# power.net
KiCad netlist of a schematic drawn in Altium Designer
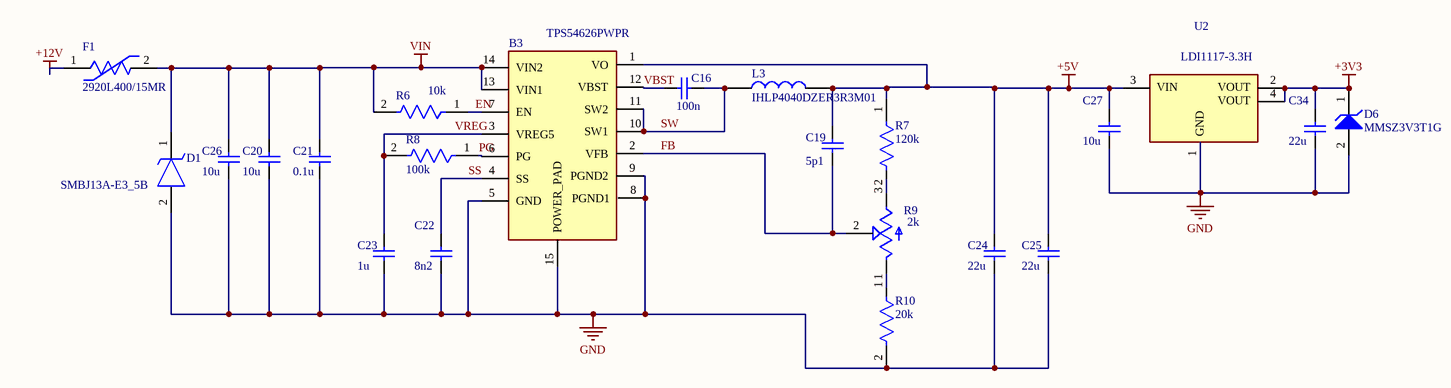
[diagram p0: power.SchDoc]

(export (version "E")
  (design (tool "Eeschema 10.0.6"))
  (components
    (comp (ref "B3")
      (value "TPS54626PWPR")
      (footprint "TPS54626PWPR")
      (fields
        (field (name "MOUSER PART NUMBER") "595-TPS54626PWPR")
        (field (name "MANUFACTURER") "Texas Instruments")
      )
      (libsource (lib "HydrogreenLibrary") (part "TPS54626PWPR"))
    )
    (comp (ref "C16")
      (value "100n")
      (footprint "CAPC1206(3216)150_L")
      (description "CAP 1.8uF 10V ±5% 1206 (3216 Metric) Thickness 1.45mm SMD")
      (fields (field (name "TOLERANCE") "Â±5%"))
      (libsource (lib "Altium Content Vault") (part "CAP"))
    )
    (comp (ref "C19")
      (value "5p1")
      (footprint "CAPC1206(3216)150_L")
      (description "CAP 1.8uF 10V ±5% 1206 (3216 Metric) Thickness 1.45mm SMD")
      (fields (field (name "TOLERANCE") "Â±5%"))
      (libsource (lib "Altium Content Vault") (part "CAP"))
    )
    (comp (ref "C20")
      (value "10u")
      (footprint "CAPC1206(3216)150_L")
      (description "CAP 1.8uF 10V ±5% 1206 (3216 Metric) Thickness 1.45mm SMD")
      (fields (field (name "TOLERANCE") "Â±5%"))
      (libsource (lib "Altium Content Vault") (part "CAP"))
    )
    (comp (ref "C21")
      (value "0.1u")
      (footprint "CAPC1206(3216)150_L")
      (description "CAP 1.8uF 10V ±5% 1206 (3216 Metric) Thickness 1.45mm SMD")
      (fields (field (name "TOLERANCE") "Â±5%"))
      (libsource (lib "Altium Content Vault") (part "CAP"))
    )
    (comp (ref "C22")
      (value "8n2")
      (footprint "CAPC1206(3216)150_L")
      (description "CAP 1.8uF 10V ±5% 1206 (3216 Metric) Thickness 1.45mm SMD")
      (fields (field (name "TOLERANCE") "Â±5%"))
      (libsource (lib "Altium Content Vault") (part "CAP"))
    )
    (comp (ref "C23")
      (value "1u")
      (footprint "CAPC1206(3216)150_L")
      (description "CAP 1.8uF 10V ±5% 1206 (3216 Metric) Thickness 1.45mm SMD")
      (fields (field (name "TOLERANCE") "Â±5%"))
      (libsource (lib "Altium Content Vault") (part "CAP"))
    )
    (comp (ref "C24")
      (value "22u")
      (footprint "CAPC1206(3216)150_L")
      (description "CAP 1.8uF 10V ±5% 1206 (3216 Metric) Thickness 1.45mm SMD")
      (fields (field (name "TOLERANCE") "Â±5%"))
      (libsource (lib "Altium Content Vault") (part "CAP"))
    )
    (comp (ref "C25")
      (value "22u")
      (footprint "CAPC1206(3216)150_L")
      (description "CAP 1.8uF 10V ±5% 1206 (3216 Metric) Thickness 1.45mm SMD")
      (fields (field (name "TOLERANCE") "Â±5%"))
      (libsource (lib "Altium Content Vault") (part "CAP"))
    )
    (comp (ref "C26")
      (value "10u")
      (footprint "CAPC1206(3216)150_L")
      (description "CAP 1.8uF 10V ±5% 1206 (3216 Metric) Thickness 1.45mm SMD")
      (fields (field (name "TOLERANCE") "Â±5%"))
      (libsource (lib "Altium Content Vault") (part "CAP"))
    )
    (comp (ref "C27")
      (value "10u")
      (footprint "CAPC1206(3216)150_L")
      (description "CAP 1.8uF 10V ±5% 1206 (3216 Metric) Thickness 1.45mm SMD")
      (fields (field (name "TOLERANCE") "Â±5%"))
      (libsource (lib "Altium Content Vault") (part "CAP"))
    )
    (comp (ref "C34")
      (value "22u")
      (footprint "CAPC1206(3216)150_L")
      (description "CAP 1.8uF 10V ±5% 1206 (3216 Metric) Thickness 1.45mm SMD")
      (fields (field (name "TOLERANCE") "Â±5%"))
      (libsource (lib "Altium Content Vault") (part "CAP"))
    )
    (comp (ref "D1")
      (value "SMBJ13A-E3_5B")
      (footprint "SamacSys:DIOM5436X244N")
      (description "TVS Diode (Uni-directional)")
      (fields
        (field (name "MANUFACTURER_PART_NUMBER") "SMBJ13A-E3/5B")
        (field (name "MOUSER PART NUMBER") "625-SMBJ13A-E3/5B")
      )
      (libsource (lib "*") (part "SMBJ13A-E3_5B"))
    )
    (comp (ref "D6")
      (value "MMSZ3V3T1G")
      (footprint "ONSC-SOD-123-2-425-04_V")
      (description "Zener Voltage Regulator, 500 mW, 2-Pin SOD-123, Pb-Free, Tape and Reel")
      (fields (field (name "MANUFACTURER") "On Semiconductor"))
      (libsource (lib "Altium Content Vault") (part "ONSC-K1A2-2"))
    )
    (comp (ref "F1")
      (value "2920L400/15MR")
      (footprint "FP-2920L400-15MR-MFG")
      (description "PTC RESET FUSE 15V 4A 2920")
      (libsource (lib "Altium Content Vault") (part "fc31388045fc42ab786d6d00b506e9f"))
    )
    (comp (ref "L3")
      (value "IHLP4040DZER3R3M01")
      (footprint "IHLP4040DZER3R3M01")
      (description "Inductor High Current Shielded Wirewound 3.3uH 20% 100KHz 10A 11.8mOhm DCR 4040 T/R")
      (fields
        (field (name "MOUSER PART NUMBER") "70-IHLP4040DZER3R3M0")
        (field (name "MANUFACTURER") "Vishay")
      )
      (libsource (lib "HydrogreenLibrary") (part "IHLP4040DZER3R3M01"))
    )
    (comp (ref "R6")
      (value "10k")
      (footprint "FP-RK73H2B-MFG")
      (description "40.2kΩ ±1% 0.25W Chip Resistor 1206 Thick Film AEC-Q200 Qualified")
      (fields (field (name "TOLERANCE") "1%"))
      (libsource (lib "Altium Content Vault") (part "1029c3af85768c4190bb7ad29bc67b5"))
    )
    (comp (ref "R7")
      (value "120k")
      (footprint "FP-RK73H2B-MFG")
      (description "40.2kΩ ±1% 0.25W Chip Resistor 1206 Thick Film AEC-Q200 Qualified")
      (fields (field (name "TOLERANCE") "1%"))
      (libsource (lib "Altium Content Vault") (part "1029c3af85768c4190bb7ad29bc67b5"))
    )
    (comp (ref "R8")
      (value "100k")
      (footprint "FP-RK73H2B-MFG")
      (description "40.2kΩ ±1% 0.25W Chip Resistor 1206 Thick Film AEC-Q200 Qualified")
      (fields (field (name "TOLERANCE") "1%"))
      (libsource (lib "Altium Content Vault") (part "1029c3af85768c4190bb7ad29bc67b5"))
    )
    (comp (ref "R9")
      (value "2k")
      (footprint "TRIM_TC33X-2-503E")
      (description "Adjustable Resistors – SMD; BOURNS; TC33X-2-503E; Cermet; 1.2 mm; 100 mW; Surface Mount")
      (fields (field (name "MP") "TC33X-2-503E") (field (name "MF") "Bourns"))
      (libsource (lib "HydrogreenLibrary") (part "TC33X-2-503E"))
    )
    (comp (ref "R10")
      (value "20k")
      (footprint "FP-RK73H2B-MFG")
      (description "40.2kΩ ±1% 0.25W Chip Resistor 1206 Thick Film AEC-Q200 Qualified")
      (fields (field (name "TOLERANCE") "1%"))
      (libsource (lib "Altium Content Vault") (part "1029c3af85768c4190bb7ad29bc67b5"))
    )
    (comp (ref "U2")
      (value "LDI1117-3.3H")
      (footprint "LDI1117-3.3H")
      (description "Fixed Positive LDO Regulator")
      (fields (field (name "MANUFACTURER") "Diotec"))
      (libsource (lib "HydrogreenLibrary") (part "LDI1117-3.3H"))
    )
  )
  (nets
    (net (code "1") (name "+3V3") (class "Default")
      (node (ref "C34") (pin "1") (pinfunction "1_1") (pintype "passive"))
      (node (ref "D6") (pin "1") (pinfunction "K_1") (pintype "passive"))
      (node (ref "U2") (pin "2") (pintype "power_in"))
      (node (ref "U2") (pin "4") (pintype "power_in"))
    )
    (net (code "2") (name "+5V") (class "Default")
      (node (ref "B3") (pin "1") (pinfunction "VO_1") (pintype "passive"))
      (node (ref "C19") (pin "1") (pinfunction "1_1") (pintype "passive"))
      (node (ref "C24") (pin "1") (pinfunction "1_1") (pintype "passive"))
      (node (ref "C25") (pin "1") (pinfunction "1_1") (pintype "passive"))
      (node (ref "C27") (pin "1") (pinfunction "1_1") (pintype "passive"))
      (node (ref "L3") (pin "2") (pinfunction "2_2") (pintype "passive"))
      (node (ref "R7") (pin "1") (pinfunction "1_1") (pintype "passive"))
      (node (ref "U2") (pin "3") (pintype "power_in"))
    )
    (net (code "3") (name "+12V") (class "Default")
      (node (ref "F1") (pin "1") (pinfunction "1_1") (pintype "passive"))
    )
    (net (code "4") (name "/EN") (class "Default")
      (node (ref "B3") (pin "7") (pinfunction "EN_7") (pintype "passive"))
      (node (ref "R6") (pin "1") (pinfunction "1_1") (pintype "passive"))
    )
    (net (code "5") (name "/FB") (class "Default")
      (node (ref "B3") (pin "2") (pinfunction "VFB_2") (pintype "passive"))
      (node (ref "C19") (pin "2") (pinfunction "2_2") (pintype "passive"))
      (node (ref "R9") (pin "2") (pinfunction "W_2") (pintype "passive"))
    )
    (net (code "6") (name "/PG") (class "Default")
      (node (ref "B3") (pin "6") (pinfunction "PG_6") (pintype "passive"))
      (node (ref "R8") (pin "1") (pinfunction "1_1") (pintype "passive"))
    )
    (net (code "7") (name "/SS") (class "Default")
      (node (ref "B3") (pin "4") (pinfunction "SS_4") (pintype "passive"))
      (node (ref "C22") (pin "1") (pinfunction "1_1") (pintype "passive"))
    )
    (net (code "8") (name "/SW") (class "Default")
      (node (ref "B3") (pin "10") (pinfunction "SW1_10") (pintype "passive"))
      (node (ref "B3") (pin "11") (pinfunction "SW2_11") (pintype "passive"))
      (node (ref "C16") (pin "2") (pinfunction "2_2") (pintype "passive"))
      (node (ref "L3") (pin "1") (pinfunction "1_1") (pintype "passive"))
    )
    (net (code "9") (name "/VBST") (class "Default")
      (node (ref "B3") (pin "12") (pinfunction "VBST_12") (pintype "passive"))
      (node (ref "C16") (pin "1") (pinfunction "1_1") (pintype "passive"))
    )
    (net (code "10") (name "/VREG") (class "Default")
      (node (ref "B3") (pin "3") (pinfunction "VREG5_3") (pintype "passive"))
      (node (ref "C23") (pin "1") (pinfunction "1_1") (pintype "passive"))
      (node (ref "R8") (pin "2") (pinfunction "2_2") (pintype "passive"))
    )
    (net (code "11") (name "GND") (class "Default")
      (node (ref "B3") (pin "15") (pinfunction "POWER_PAD_15") (pintype "passive"))
      (node (ref "B3") (pin "5") (pinfunction "GND_5") (pintype "passive"))
      (node (ref "B3") (pin "8") (pinfunction "PGND1_8") (pintype "passive"))
      (node (ref "B3") (pin "9") (pinfunction "PGND2_9") (pintype "passive"))
      (node (ref "C20") (pin "2") (pinfunction "2_2") (pintype "passive"))
      (node (ref "C21") (pin "2") (pinfunction "2_2") (pintype "passive"))
      (node (ref "C22") (pin "2") (pinfunction "2_2") (pintype "passive"))
      (node (ref "C23") (pin "2") (pinfunction "2_2") (pintype "passive"))
      (node (ref "C24") (pin "2") (pinfunction "2_2") (pintype "passive"))
      (node (ref "C25") (pin "2") (pinfunction "2_2") (pintype "passive"))
      (node (ref "C26") (pin "2") (pinfunction "2_2") (pintype "passive"))
      (node (ref "C27") (pin "2") (pinfunction "2_2") (pintype "passive"))
      (node (ref "C34") (pin "2") (pinfunction "2_2") (pintype "passive"))
      (node (ref "D1") (pin "2") (pinfunction "A_2") (pintype "passive"))
      (node (ref "D6") (pin "2") (pinfunction "A_2") (pintype "passive"))
      (node (ref "R10") (pin "2") (pinfunction "2_2") (pintype "passive"))
      (node (ref "U2") (pin "1") (pintype "passive"))
    )
    (net (code "12") (name "Net-(R9-CCW)") (class "Default")
      (node (ref "R10") (pin "1") (pinfunction "1_1") (pintype "passive"))
      (node (ref "R9") (pin "1") (pinfunction "CCW_1") (pintype "passive"))
    )
    (net (code "13") (name "Net-(R9-CW)") (class "Default")
      (node (ref "R7") (pin "2") (pinfunction "2_2") (pintype "passive"))
      (node (ref "R9") (pin "3") (pinfunction "CW_3") (pintype "passive"))
    )
    (net (code "14") (name "VIN") (class "Default")
      (node (ref "B3") (pin "13") (pinfunction "VIN1_13") (pintype "passive"))
      (node (ref "B3") (pin "14") (pinfunction "VIN2_14") (pintype "passive"))
      (node (ref "C20") (pin "1") (pinfunction "1_1") (pintype "passive"))
      (node (ref "C21") (pin "1") (pinfunction "1_1") (pintype "passive"))
      (node (ref "C26") (pin "1") (pinfunction "1_1") (pintype "passive"))
      (node (ref "D1") (pin "1") (pinfunction "K_1") (pintype "passive"))
      (node (ref "F1") (pin "2") (pinfunction "2_2") (pintype "passive"))
      (node (ref "R6") (pin "2") (pinfunction "2_2") (pintype "passive"))
    )
  )
)
